# Sheet1.net
KiCad netlist of a schematic drawn in Altium Designer
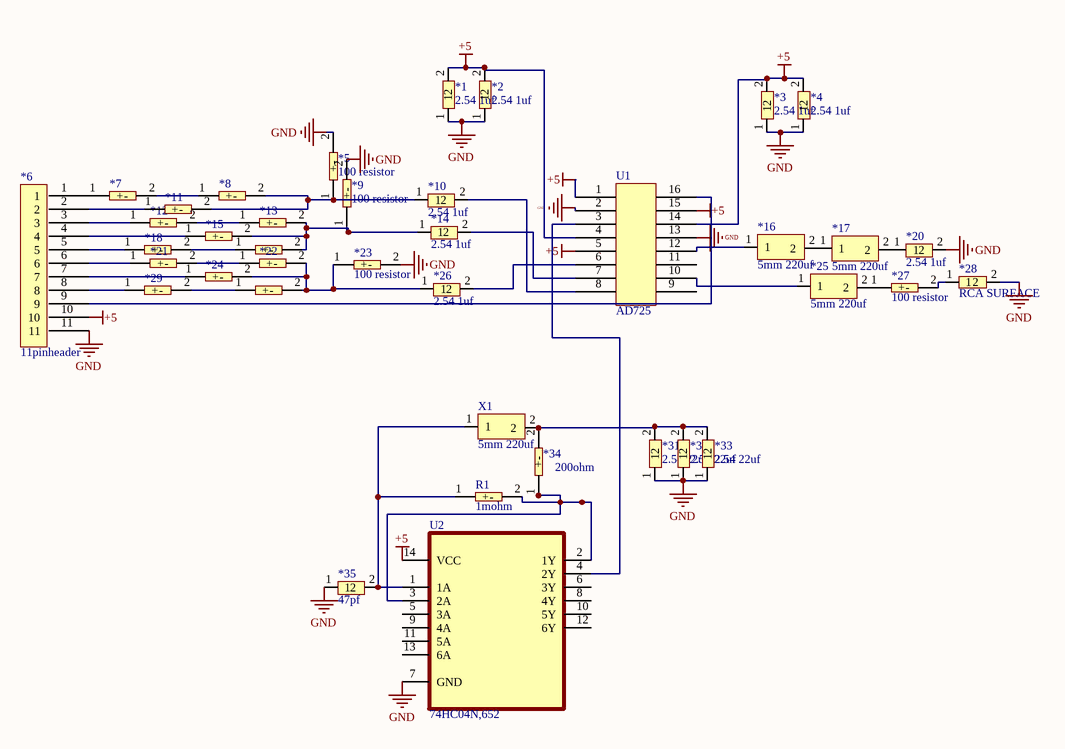
[diagram p0: Sheet1.SchDoc]

(export (version "E")
  (design (tool "Eeschema 10.0.6"))
  (components
    (comp (ref "*1")
      (value "2.54 1uf")
      (footprint "2.54mm 1uf")
      (libsource (lib "Schlib2") (part "2.54 1uf"))
    )
    (comp (ref "*2")
      (value "2.54 1uf")
      (footprint "2.54mm 1uf")
      (libsource (lib "Schlib2") (part "2.54 1uf"))
    )
    (comp (ref "*3")
      (value "2.54 1uf")
      (footprint "2.54mm 1uf")
      (libsource (lib "Schlib2") (part "2.54 1uf"))
    )
    (comp (ref "*4")
      (value "2.54 1uf")
      (footprint "2.54mm 1uf")
      (libsource (lib "Schlib2") (part "2.54 1uf"))
    )
    (comp (ref "*5")
      (value "100 resistor")
      (footprint "100 resistor")
      (libsource (lib "") (part "100 resistor_1"))
    )
    (comp (ref "*6")
      (value "11pinheader")
      (footprint "11xpinheader")
      (libsource (lib "Schlib2") (part "11pinheader"))
    )
    (comp (ref "*7")
      (value "100 resistor")
      (footprint "100 resistor")
      (libsource (lib "Schlib2") (part "100 resistor"))
    )
    (comp (ref "*8")
      (value "100 resistor")
      (footprint "100 resistor")
      (libsource (lib "Schlib2") (part "100 resistor"))
    )
    (comp (ref "*9")
      (value "100 resistor")
      (footprint "100 resistor")
      (libsource (lib "") (part "100 resistor_1"))
    )
    (comp (ref "*10") (value "2.54 1uf") (footprint "2.54mm 1uf") (libsource (lib "") (part "2.54 1uf_1")))
    (comp (ref "*11")
      (value "100 resistor")
      (footprint "100 resistor")
      (libsource (lib "Schlib2") (part "100 resistor"))
    )
    (comp (ref "*12")
      (value "100 resistor")
      (footprint "100 resistor")
      (libsource (lib "Schlib2") (part "100 resistor"))
    )
    (comp (ref "*13")
      (value "100 resistor")
      (footprint "100 resistor")
      (libsource (lib "Schlib2") (part "100 resistor"))
    )
    (comp (ref "*14") (value "2.54 1uf") (footprint "2.54mm 1uf") (libsource (lib "") (part "2.54 1uf_1")))
    (comp (ref "*15")
      (value "100 resistor")
      (footprint "100 resistor")
      (libsource (lib "Schlib2") (part "100 resistor"))
    )
    (comp (ref "*16")
      (value "5mm 220uf")
      (footprint "5mm 220uF")
      (libsource (lib "Schlib2") (part "5mm 220uf"))
    )
    (comp (ref "*17")
      (value "5mm 220uf")
      (footprint "5mm 220uF")
      (libsource (lib "Schlib2") (part "5mm 220uf"))
    )
    (comp (ref "*18")
      (value "100 resistor")
      (footprint "100 resistor")
      (libsource (lib "Schlib2") (part "100 resistor"))
    )
    (comp (ref "*19")
      (value "100 resistor")
      (footprint "100 resistor")
      (libsource (lib "Schlib2") (part "100 resistor"))
    )
    (comp (ref "*20") (value "2.54 1uf") (footprint "2.54mm 1uf") (libsource (lib "") (part "2.54 1uf_1")))
    (comp (ref "*21")
      (value "100 resistor")
      (footprint "100 resistor")
      (libsource (lib "Schlib2") (part "100 resistor"))
    )
    (comp (ref "*22")
      (value "100 resistor")
      (footprint "100 resistor")
      (libsource (lib "Schlib2") (part "100 resistor"))
    )
    (comp (ref "*23")
      (value "100 resistor")
      (footprint "100 resistor")
      (libsource (lib "Schlib2") (part "100 resistor"))
    )
    (comp (ref "*24")
      (value "100 resistor")
      (footprint "100 resistor")
      (libsource (lib "Schlib2") (part "100 resistor"))
    )
    (comp (ref "*25")
      (value "5mm 220uf")
      (footprint "5mm 220uF")
      (libsource (lib "Schlib2") (part "5mm 220uf"))
    )
    (comp (ref "*26") (value "2.54 1uf") (footprint "2.54mm 1uf") (libsource (lib "") (part "2.54 1uf_1")))
    (comp (ref "*27")
      (value "100 resistor")
      (footprint "100 resistor")
      (libsource (lib "Schlib2") (part "100 resistor"))
    )
    (comp (ref "*28")
      (value "RCA SURFACE")
      (footprint "RCA SURFACE")
      (libsource (lib "Schlib2") (part "RCA SURFACE"))
    )
    (comp (ref "*29")
      (value "100 resistor")
      (footprint "100 resistor")
      (libsource (lib "Schlib2") (part "100 resistor"))
    )
    (comp (ref "*30")
      (value "100 resistor")
      (footprint "100 resistor")
      (libsource (lib "Schlib2") (part "100 resistor"))
    )
    (comp (ref "*31")
      (value "2.54 22uf")
      (footprint "2.54mm 1uf")
      (libsource (lib "Schlib2") (part "2.54 1uf"))
    )
    (comp (ref "*32")
      (value "2.54 22uf")
      (footprint "2.54mm 1uf")
      (libsource (lib "Schlib2") (part "2.54 1uf"))
    )
    (comp (ref "*33")
      (value "2.54 22uf")
      (footprint "2.54mm 1uf")
      (libsource (lib "Schlib2") (part "2.54 1uf"))
    )
    (comp (ref "*34")
      (value "200ohm")
      (footprint "100 resistor")
      (libsource (lib "") (part "100 resistor_1"))
    )
    (comp (ref "*35") (value "47pf") (footprint "2.54mm 1uf") (libsource (lib "") (part "2.54 1uf_1")))
    (comp (ref "R1")
      (value "1mohm")
      (footprint "100 resistor")
      (libsource (lib "Schlib2") (part "100 resistor"))
    )
    (comp (ref "U1") (value "AD725") (footprint "AD725 SOIC16") (libsource (lib "Schlib2") (part "AD725")))
    (comp (ref "U2")
      (value "74HC04N,652")
      (footprint "DIP254P762X420-14")
      (description "Inverter IC 6 Channel 14-DIP")
      (fields (field (name "MF") "NXP USA"))
      (libsource (lib "Schlib2") (part "74HC04N,652"))
    )
    (comp (ref "X1")
      (value "5mm 220uf")
      (footprint "5mm 220uF")
      (libsource (lib "Schlib2") (part "5mm 220uf"))
    )
  )
  (nets
    (net (code "1") (name "+5") (class "Default")
      (node (ref "*1") (pin "2") (pinfunction "2_2") (pintype "passive"))
      (node (ref "*2") (pin "2") (pinfunction "2_2") (pintype "passive"))
      (node (ref "*3") (pin "2") (pinfunction "2_2") (pintype "passive"))
      (node (ref "*4") (pin "2") (pinfunction "2_2") (pintype "passive"))
      (node (ref "*6") (pin "10") (pinfunction "10_10") (pintype "passive"))
      (node (ref "U1") (pin "1") (pintype "passive"))
      (node (ref "U1") (pin "14") (pintype "passive"))
      (node (ref "U1") (pin "15") (pintype "passive"))
      (node (ref "U1") (pin "4") (pintype "passive"))
      (node (ref "U1") (pin "5") (pintype "passive"))
      (node (ref "U2") (pin "14") (pinfunction "VCC_14") (pintype "passive"))
    )
    (net (code "2") (name "GND") (class "Default")
      (node (ref "*1") (pin "1") (pinfunction "1_1") (pintype "passive"))
      (node (ref "*2") (pin "1") (pinfunction "1_1") (pintype "passive"))
      (node (ref "*20") (pin "2") (pinfunction "2_2") (pintype "passive"))
      (node (ref "*23") (pin "2") (pinfunction "-_2") (pintype "passive"))
      (node (ref "*28") (pin "2") (pinfunction "2_2") (pintype "passive"))
      (node (ref "*3") (pin "1") (pinfunction "1_1") (pintype "passive"))
      (node (ref "*31") (pin "1") (pinfunction "1_1") (pintype "passive"))
      (node (ref "*32") (pin "1") (pinfunction "1_1") (pintype "passive"))
      (node (ref "*33") (pin "1") (pinfunction "1_1") (pintype "passive"))
      (node (ref "*35") (pin "1") (pinfunction "1_1") (pintype "passive"))
      (node (ref "*4") (pin "1") (pinfunction "1_1") (pintype "passive"))
      (node (ref "*5") (pin "2") (pinfunction "-_2") (pintype "passive"))
      (node (ref "*6") (pin "11") (pinfunction "11_11") (pintype "passive"))
      (node (ref "*9") (pin "2") (pinfunction "-_2") (pintype "passive"))
      (node (ref "U1") (pin "13") (pintype "passive"))
      (node (ref "U1") (pin "2") (pintype "passive"))
      (node (ref "U2") (pin "7") (pinfunction "GND_7") (pintype "passive"))
    )
    (net (code "3") (name "Net-(*6-Pad9)") (class "Default")
      (node (ref "*6") (pin "9") (pinfunction "9_9") (pintype "passive"))
      (node (ref "U1") (pin "16") (pintype "passive"))
    )
    (net (code "4") (name "Net-(*7-+)") (class "Default")
      (node (ref "*6") (pin "1") (pinfunction "1_1") (pintype "passive"))
      (node (ref "*7") (pin "1") (pinfunction "+_1") (pintype "passive"))
    )
    (net (code "5") (name "Net-(*7--)") (class "Default")
      (node (ref "*7") (pin "2") (pinfunction "-_2") (pintype "passive"))
      (node (ref "*8") (pin "1") (pinfunction "+_1") (pintype "passive"))
    )
    (net (code "6") (name "Net-(*10-Pad2)") (class "Default")
      (node (ref "*10") (pin "2") (pinfunction "2_2") (pintype "passive"))
      (node (ref "U1") (pin "8") (pintype "passive"))
    )
    (net (code "7") (name "Net-(*11-+)") (class "Default")
      (node (ref "*11") (pin "1") (pinfunction "+_1") (pintype "passive"))
      (node (ref "*6") (pin "2") (pinfunction "2_2") (pintype "passive"))
    )
    (net (code "8") (name "Net-(*11--)") (class "Default")
      (node (ref "*10") (pin "1") (pinfunction "1_1") (pintype "passive"))
      (node (ref "*11") (pin "2") (pinfunction "-_2") (pintype "passive"))
      (node (ref "*5") (pin "1") (pinfunction "+_1") (pintype "passive"))
      (node (ref "*8") (pin "2") (pinfunction "-_2") (pintype "passive"))
    )
    (net (code "9") (name "Net-(*12-+)") (class "Default")
      (node (ref "*12") (pin "1") (pinfunction "+_1") (pintype "passive"))
      (node (ref "*6") (pin "3") (pinfunction "3_3") (pintype "passive"))
    )
    (net (code "10") (name "Net-(*12--)") (class "Default")
      (node (ref "*12") (pin "2") (pinfunction "-_2") (pintype "passive"))
      (node (ref "*13") (pin "1") (pinfunction "+_1") (pintype "passive"))
    )
    (net (code "11") (name "Net-(*13--)") (class "Default")
      (node (ref "*13") (pin "2") (pinfunction "-_2") (pintype "passive"))
      (node (ref "*14") (pin "1") (pinfunction "1_1") (pintype "passive"))
      (node (ref "*15") (pin "2") (pinfunction "-_2") (pintype "passive"))
      (node (ref "*19") (pin "2") (pinfunction "-_2") (pintype "passive"))
      (node (ref "*9") (pin "1") (pinfunction "+_1") (pintype "passive"))
    )
    (net (code "12") (name "Net-(*14-Pad2)") (class "Default")
      (node (ref "*14") (pin "2") (pinfunction "2_2") (pintype "passive"))
      (node (ref "U1") (pin "7") (pintype "passive"))
    )
    (net (code "13") (name "Net-(*15-+)") (class "Default")
      (node (ref "*15") (pin "1") (pinfunction "+_1") (pintype "passive"))
      (node (ref "*6") (pin "4") (pinfunction "4_4") (pintype "passive"))
    )
    (net (code "14") (name "Net-(*16-Pad1)") (class "Default")
      (node (ref "*16") (pin "1") (pinfunction "1_1") (pintype "passive"))
      (node (ref "U1") (pin "12") (pintype "passive"))
    )
    (net (code "15") (name "Net-(*16-Pad2)") (class "Default")
      (node (ref "*16") (pin "2") (pinfunction "2_2") (pintype "passive"))
      (node (ref "*17") (pin "1") (pinfunction "1_1") (pintype "passive"))
    )
    (net (code "16") (name "Net-(*17-Pad2)") (class "Default")
      (node (ref "*17") (pin "2") (pinfunction "2_2") (pintype "passive"))
      (node (ref "*20") (pin "1") (pinfunction "1_1") (pintype "passive"))
    )
    (net (code "17") (name "Net-(*18-+)") (class "Default")
      (node (ref "*18") (pin "1") (pinfunction "+_1") (pintype "passive"))
      (node (ref "*6") (pin "5") (pinfunction "5_5") (pintype "passive"))
    )
    (net (code "18") (name "Net-(*18--)") (class "Default")
      (node (ref "*18") (pin "2") (pinfunction "-_2") (pintype "passive"))
      (node (ref "*19") (pin "1") (pinfunction "+_1") (pintype "passive"))
    )
    (net (code "19") (name "Net-(*21-+)") (class "Default")
      (node (ref "*21") (pin "1") (pinfunction "+_1") (pintype "passive"))
      (node (ref "*6") (pin "6") (pinfunction "6_6") (pintype "passive"))
    )
    (net (code "20") (name "Net-(*21--)") (class "Default")
      (node (ref "*21") (pin "2") (pinfunction "-_2") (pintype "passive"))
      (node (ref "*22") (pin "1") (pinfunction "+_1") (pintype "passive"))
    )
    (net (code "21") (name "Net-(*22--)") (class "Default")
      (node (ref "*22") (pin "2") (pinfunction "-_2") (pintype "passive"))
      (node (ref "*23") (pin "1") (pinfunction "+_1") (pintype "passive"))
      (node (ref "*24") (pin "2") (pinfunction "-_2") (pintype "passive"))
      (node (ref "*26") (pin "1") (pinfunction "1_1") (pintype "passive"))
      (node (ref "*30") (pin "2") (pinfunction "-_2") (pintype "passive"))
    )
    (net (code "22") (name "Net-(*24-+)") (class "Default")
      (node (ref "*24") (pin "1") (pinfunction "+_1") (pintype "passive"))
      (node (ref "*6") (pin "7") (pinfunction "7_7") (pintype "passive"))
    )
    (net (code "23") (name "Net-(*25-Pad1)") (class "Default")
      (node (ref "*25") (pin "1") (pinfunction "1_1") (pintype "passive"))
      (node (ref "U1") (pin "10") (pintype "passive"))
    )
    (net (code "24") (name "Net-(*26-Pad2)") (class "Default")
      (node (ref "*26") (pin "2") (pinfunction "2_2") (pintype "passive"))
      (node (ref "U1") (pin "6") (pintype "passive"))
    )
    (net (code "25") (name "Net-(*27-+)") (class "Default")
      (node (ref "*25") (pin "2") (pinfunction "2_2") (pintype "passive"))
      (node (ref "*27") (pin "1") (pinfunction "+_1") (pintype "passive"))
    )
    (net (code "26") (name "Net-(*27--)") (class "Default")
      (node (ref "*27") (pin "2") (pinfunction "-_2") (pintype "passive"))
      (node (ref "*28") (pin "1") (pinfunction "1_1") (pintype "passive"))
    )
    (net (code "27") (name "Net-(*29-+)") (class "Default")
      (node (ref "*29") (pin "1") (pinfunction "+_1") (pintype "passive"))
      (node (ref "*6") (pin "8") (pinfunction "8_8") (pintype "passive"))
    )
    (net (code "28") (name "Net-(*29--)") (class "Default")
      (node (ref "*29") (pin "2") (pinfunction "-_2") (pintype "passive"))
      (node (ref "*30") (pin "1") (pinfunction "+_1") (pintype "passive"))
    )
    (net (code "29") (name "Net-(*34-+)") (class "Default")
      (node (ref "*34") (pin "1") (pinfunction "+_1") (pintype "passive"))
      (node (ref "R1") (pin "2") (pinfunction "-_2") (pintype "passive"))
      (node (ref "U2") (pin "2") (pinfunction "1Y_2") (pintype "passive"))
      (node (ref "U2") (pin "3") (pinfunction "2A_3") (pintype "passive"))
    )
    (net (code "30") (name "Net-(*34--)") (class "Default")
      (node (ref "*31") (pin "2") (pinfunction "2_2") (pintype "passive"))
      (node (ref "*32") (pin "2") (pinfunction "2_2") (pintype "passive"))
      (node (ref "*33") (pin "2") (pinfunction "2_2") (pintype "passive"))
      (node (ref "*34") (pin "2") (pinfunction "-_2") (pintype "passive"))
      (node (ref "X1") (pin "2") (pinfunction "2_2") (pintype "passive"))
    )
    (net (code "31") (name "Net-(R1-+)") (class "Default")
      (node (ref "*35") (pin "2") (pinfunction "2_2") (pintype "passive"))
      (node (ref "R1") (pin "1") (pinfunction "+_1") (pintype "passive"))
      (node (ref "U2") (pin "1") (pinfunction "1A_1") (pintype "passive"))
      (node (ref "X1") (pin "1") (pinfunction "1_1") (pintype "passive"))
    )
    (net (code "32") (name "Net-(U2-2Y)") (class "Default")
      (node (ref "U1") (pin "3") (pintype "passive"))
      (node (ref "U2") (pin "4") (pinfunction "2Y_4") (pintype "passive"))
    )
    (net (code "33") (name "unconnected-(U1-Pad9)") (class "Default")
      (node (ref "U1") (pin "9") (pintype "passive"))
    )
    (net (code "34") (name "unconnected-(U1-Pad11)") (class "Default")
      (node (ref "U1") (pin "11") (pintype "passive"))
    )
    (net (code "35") (name "unconnected-(U2-3A-Pad5)") (class "Default")
      (node (ref "U2") (pin "5") (pinfunction "3A_5") (pintype "passive"))
    )
    (net (code "36") (name "unconnected-(U2-3Y-Pad6)") (class "Default")
      (node (ref "U2") (pin "6") (pinfunction "3Y_6") (pintype "passive"))
    )
    (net (code "37") (name "unconnected-(U2-4A-Pad9)") (class "Default")
      (node (ref "U2") (pin "9") (pinfunction "4A_9") (pintype "passive"))
    )
    (net (code "38") (name "unconnected-(U2-4Y-Pad8)") (class "Default")
      (node (ref "U2") (pin "8") (pinfunction "4Y_8") (pintype "passive"))
    )
    (net (code "39") (name "unconnected-(U2-5A-Pad11)") (class "Default")
      (node (ref "U2") (pin "11") (pinfunction "5A_11") (pintype "passive"))
    )
    (net (code "40") (name "unconnected-(U2-5Y-Pad10)") (class "Default")
      (node (ref "U2") (pin "10") (pinfunction "5Y_10") (pintype "passive"))
    )
    (net (code "41") (name "unconnected-(U2-6A-Pad13)") (class "Default")
      (node (ref "U2") (pin "13") (pinfunction "6A_13") (pintype "passive"))
    )
    (net (code "42") (name "unconnected-(U2-6Y-Pad12)") (class "Default")
      (node (ref "U2") (pin "12") (pinfunction "6Y_12") (pintype "passive"))
    )
  )
)
